# 12VPart.net
KiCad netlist of a schematic drawn in EAGLE
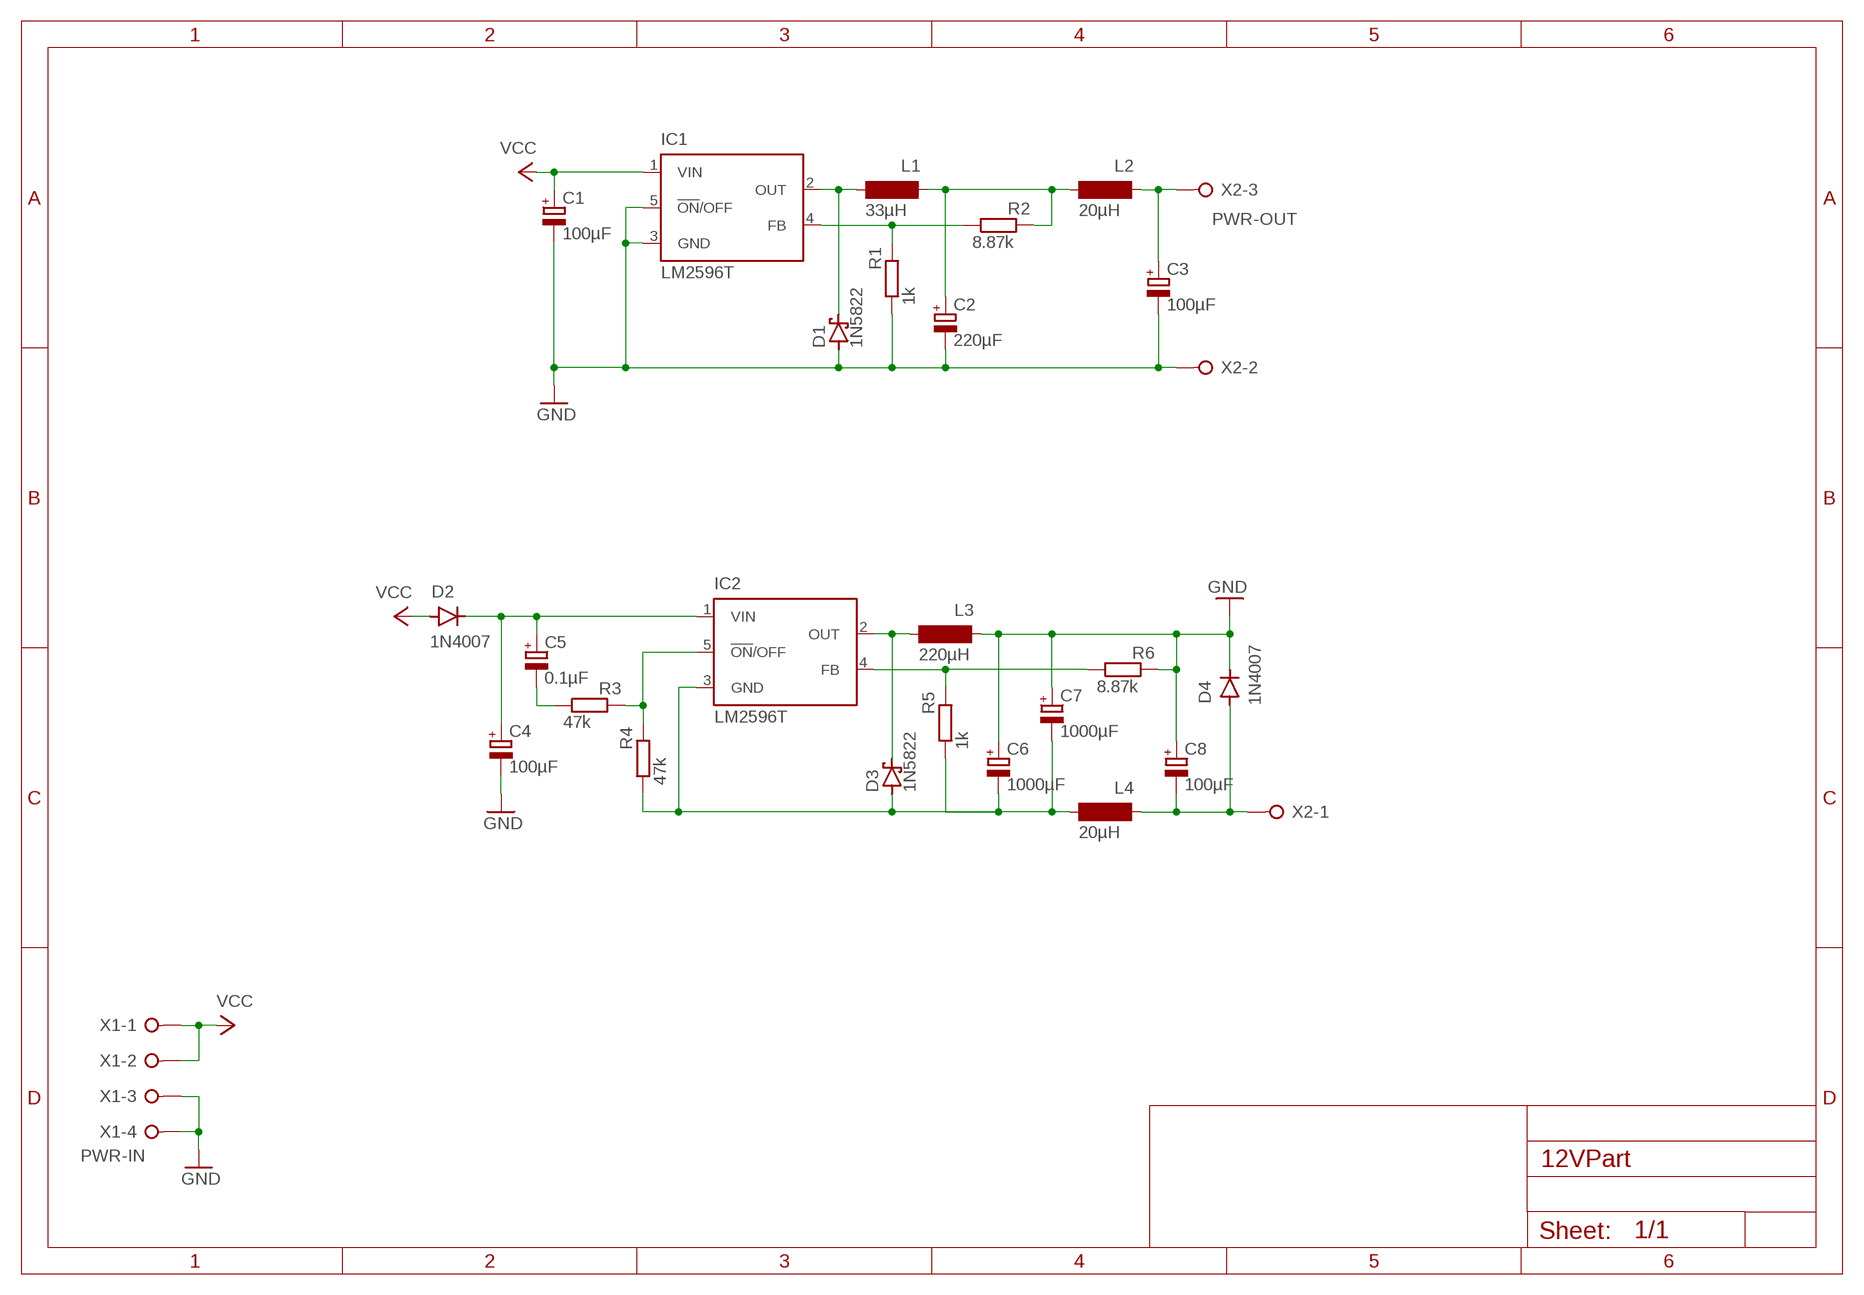
[diagram p0: schematic, sheet 1]

(export (version "E")
  (design (tool "Eeschema 10.0.6"))
  (components
    (comp (ref "C1")
      (value "100µF")
      (footprint "eagle-import:E2,5-6")
      (libsource (lib "eagle-import") (part "CPOL-EUE2.5-6"))
    )
    (comp (ref "C2")
      (value "220µF")
      (footprint "eagle-import:E2,5-6")
      (libsource (lib "eagle-import") (part "CPOL-EUE2.5-6"))
    )
    (comp (ref "C3")
      (value "100µF")
      (footprint "eagle-import:E2,5-6")
      (libsource (lib "eagle-import") (part "CPOL-EUE2.5-6"))
    )
    (comp (ref "C4")
      (value "100µF")
      (footprint "eagle-import:E2,5-6")
      (libsource (lib "eagle-import") (part "CPOL-EUE2.5-6"))
    )
    (comp (ref "C5")
      (value "0.1µF")
      (footprint "eagle-import:E2-4")
      (libsource (lib "eagle-import") (part "CPOL-EUE2-4"))
    )
    (comp (ref "C6")
      (value "1000µF")
      (footprint "eagle-import:E5-10,5")
      (libsource (lib "eagle-import") (part "CPOL-EUE5-10.5"))
    )
    (comp (ref "C7")
      (value "1000µF")
      (footprint "eagle-import:E5-10,5")
      (libsource (lib "eagle-import") (part "CPOL-EUE5-10.5"))
    )
    (comp (ref "C8")
      (value "100µF")
      (footprint "eagle-import:E2,5-6")
      (libsource (lib "eagle-import") (part "CPOL-EUE2.5-6"))
    )
    (comp (ref "D1")
      (value "1N5822")
      (footprint "eagle-import:C4111-15")
      (libsource (lib "eagle-import") (part "1N5908"))
    )
    (comp (ref "D2")
      (value "1N4007")
      (footprint "eagle-import:DO-41")
      (fields
        (field (name "DIGIKEY_PART_NUMBER") "1N4007MSCT-ND")
        (field (name "MANUFACTURER") "Micro Commercial Co")
        (field (name "CREATED_BY") "PCBLayout.com")
      )
      (libsource (lib "eagle-import") (part "1N4007"))
    )
    (comp (ref "D3")
      (value "1N5822")
      (footprint "eagle-import:C4111-15")
      (libsource (lib "eagle-import") (part "1N5908"))
    )
    (comp (ref "D4")
      (value "1N4007")
      (footprint "eagle-import:DO-41")
      (fields
        (field (name "DIGIKEY_PART_NUMBER") "1N4007MSCT-ND")
        (field (name "MANUFACTURER") "Micro Commercial Co")
        (field (name "CREATED_BY") "PCBLayout.com")
      )
      (libsource (lib "eagle-import") (part "1N4007"))
    )
    (comp (ref "IC1")
      (value "LM2596T")
      (footprint "eagle-import:T05D")
      (fields (field (name "MPN") "LM2596T-ADJ/LF02"))
      (libsource (lib "eagle-import") (part "LM2596T"))
    )
    (comp (ref "IC2")
      (value "LM2596T")
      (footprint "eagle-import:T05D")
      (fields (field (name "MPN") "LM2596T-ADJ/LF02"))
      (libsource (lib "eagle-import") (part "LM2596T"))
    )
    (comp (ref "L1")
      (value "33µH")
      (footprint "eagle-import:IND-120")
      (libsource (lib "eagle-import") (part "IND-120-330K"))
    )
    (comp (ref "L2")
      (value "20µH")
      (footprint "eagle-import:B82111B")
      (libsource (lib "eagle-import") (part "B82111B0000C020"))
    )
    (comp (ref "L3")
      (value "220µH")
      (footprint "eagle-import:11PHC")
      (libsource (lib "eagle-import") (part "11PHC-221K-50"))
    )
    (comp (ref "L4")
      (value "20µH")
      (footprint "eagle-import:B82111B")
      (libsource (lib "eagle-import") (part "B82111B0000C020"))
    )
    (comp (ref "R1")
      (value "1k")
      (footprint "eagle-import:0207_10")
      (libsource (lib "eagle-import") (part "R-EU_0207/10"))
    )
    (comp (ref "R2")
      (value "8.87k")
      (footprint "eagle-import:0207_10")
      (libsource (lib "eagle-import") (part "R-EU_0207/10"))
    )
    (comp (ref "R3")
      (value "47k")
      (footprint "eagle-import:0207_10")
      (libsource (lib "eagle-import") (part "R-EU_0207/10"))
    )
    (comp (ref "R4")
      (value "47k")
      (footprint "eagle-import:0207_10")
      (libsource (lib "eagle-import") (part "R-EU_0207/10"))
    )
    (comp (ref "R5")
      (value "1k")
      (footprint "eagle-import:0207_10")
      (libsource (lib "eagle-import") (part "R-EU_0207/10"))
    )
    (comp (ref "R6")
      (value "8.87k")
      (footprint "eagle-import:0207_10")
      (libsource (lib "eagle-import") (part "R-EU_0207/10"))
    )
    (comp (ref "X1")
      (value "PWR-IN")
      (footprint "eagle-import:W237-4P")
      (libsource (lib "eagle-import") (part "W237-04P"))
    )
    (comp (ref "X2")
      (value "PWR-OUT")
      (footprint "eagle-import:W237-133")
      (libsource (lib "eagle-import") (part "W237-03P"))
    )
  )
  (nets
    (net (code "1") (name "GND") (class "Default")
      (node (ref "C1") (pin "-") (pinfunction "-_-") (pintype "passive"))
      (node (ref "C2") (pin "-") (pinfunction "-_-") (pintype "passive"))
      (node (ref "C3") (pin "-") (pinfunction "-_-") (pintype "passive"))
      (node (ref "C4") (pin "-") (pinfunction "-_-") (pintype "passive"))
      (node (ref "C6") (pin "+") (pinfunction "+_+") (pintype "passive"))
      (node (ref "C7") (pin "+") (pinfunction "+_+") (pintype "passive"))
      (node (ref "C8") (pin "+") (pinfunction "+_+") (pintype "passive"))
      (node (ref "D1") (pin "A") (pinfunction "A_A") (pintype "passive"))
      (node (ref "D4") (pin "C") (pinfunction "C_C") (pintype "passive"))
      (node (ref "IC1") (pin "3") (pinfunction "GND_3") (pintype "power_in"))
      (node (ref "IC1") (pin "5") (pinfunction "~{ON}/OFF_5") (pintype "input"))
      (node (ref "L3") (pin "P$2") (pinfunction "2_P$2") (pintype "passive"))
      (node (ref "R1") (pin "1") (pinfunction "1_1") (pintype "passive"))
      (node (ref "R6") (pin "2") (pinfunction "2_2") (pintype "passive"))
      (node (ref "X1") (pin "3") (pinfunction "KL_3") (pintype "passive"))
      (node (ref "X1") (pin "4") (pinfunction "KL_4") (pintype "passive"))
      (node (ref "X2") (pin "2") (pinfunction "KL_2") (pintype "passive"))
    )
    (net (code "2") (name "Net-(C5-Pad-)") (class "Default")
      (node (ref "C5") (pin "-") (pinfunction "-_-") (pintype "passive"))
      (node (ref "R3") (pin "1") (pinfunction "1_1") (pintype "passive"))
    )
    (net (code "3") (name "Net-(IC1-FB)") (class "Default")
      (node (ref "IC1") (pin "4") (pinfunction "FB_4") (pintype "input"))
      (node (ref "R1") (pin "2") (pinfunction "2_2") (pintype "passive"))
      (node (ref "R2") (pin "1") (pinfunction "1_1") (pintype "passive"))
    )
    (net (code "4") (name "Net-(IC1-OUT)") (class "Default")
      (node (ref "D1") (pin "C") (pinfunction "C_C") (pintype "passive"))
      (node (ref "IC1") (pin "2") (pinfunction "OUT_2") (pintype "output"))
      (node (ref "L1") (pin "P$1") (pinfunction "1_P$1") (pintype "passive"))
    )
    (net (code "5") (name "Net-(IC2-FB)") (class "Default")
      (node (ref "IC2") (pin "4") (pinfunction "FB_4") (pintype "input"))
      (node (ref "R5") (pin "2") (pinfunction "2_2") (pintype "passive"))
      (node (ref "R6") (pin "1") (pinfunction "1_1") (pintype "passive"))
    )
    (net (code "6") (name "Net-(IC2-GND)") (class "Default")
      (node (ref "C6") (pin "-") (pinfunction "-_-") (pintype "passive"))
      (node (ref "C7") (pin "-") (pinfunction "-_-") (pintype "passive"))
      (node (ref "D3") (pin "A") (pinfunction "A_A") (pintype "passive"))
      (node (ref "IC2") (pin "3") (pinfunction "GND_3") (pintype "power_in"))
      (node (ref "L4") (pin "P$1") (pinfunction "1_P$1") (pintype "passive"))
      (node (ref "R4") (pin "1") (pinfunction "1_1") (pintype "passive"))
      (node (ref "R5") (pin "1") (pinfunction "1_1") (pintype "passive"))
    )
    (net (code "7") (name "Net-(IC2-OUT)") (class "Default")
      (node (ref "D3") (pin "C") (pinfunction "C_C") (pintype "passive"))
      (node (ref "IC2") (pin "2") (pinfunction "OUT_2") (pintype "output"))
      (node (ref "L3") (pin "P$1") (pinfunction "1_P$1") (pintype "passive"))
    )
    (net (code "8") (name "Net-(IC2-VIN)") (class "Default")
      (node (ref "C4") (pin "+") (pinfunction "+_+") (pintype "passive"))
      (node (ref "C5") (pin "+") (pinfunction "+_+") (pintype "passive"))
      (node (ref "D2") (pin "C") (pinfunction "C_C") (pintype "passive"))
      (node (ref "IC2") (pin "1") (pinfunction "VIN_1") (pintype "input"))
    )
    (net (code "9") (name "Net-(IC2-~{ON}{slash}OFF)") (class "Default")
      (node (ref "IC2") (pin "5") (pinfunction "~{ON}/OFF_5") (pintype "input"))
      (node (ref "R3") (pin "2") (pinfunction "2_2") (pintype "passive"))
      (node (ref "R4") (pin "2") (pinfunction "2_2") (pintype "passive"))
    )
    (net (code "10") (name "Net-(L1-2)") (class "Default")
      (node (ref "C2") (pin "+") (pinfunction "+_+") (pintype "passive"))
      (node (ref "L1") (pin "P$2") (pinfunction "2_P$2") (pintype "passive"))
      (node (ref "L2") (pin "P$1") (pinfunction "1_P$1") (pintype "passive"))
      (node (ref "R2") (pin "2") (pinfunction "2_2") (pintype "passive"))
    )
    (net (code "11") (name "Net-(L2-2)") (class "Default")
      (node (ref "C3") (pin "+") (pinfunction "+_+") (pintype "passive"))
      (node (ref "L2") (pin "P$2") (pinfunction "2_P$2") (pintype "passive"))
      (node (ref "X2") (pin "3") (pinfunction "KL_3") (pintype "passive"))
    )
    (net (code "12") (name "Net-(L4-2)") (class "Default")
      (node (ref "C8") (pin "-") (pinfunction "-_-") (pintype "passive"))
      (node (ref "D4") (pin "A") (pinfunction "A_A") (pintype "passive"))
      (node (ref "L4") (pin "P$2") (pinfunction "2_P$2") (pintype "passive"))
      (node (ref "X2") (pin "1") (pinfunction "KL_1") (pintype "passive"))
    )
    (net (code "13") (name "VCC") (class "Default")
      (node (ref "C1") (pin "+") (pinfunction "+_+") (pintype "passive"))
      (node (ref "D2") (pin "A") (pinfunction "A_A") (pintype "passive"))
      (node (ref "IC1") (pin "1") (pinfunction "VIN_1") (pintype "input"))
      (node (ref "X1") (pin "1") (pinfunction "KL_1") (pintype "passive"))
      (node (ref "X1") (pin "2") (pinfunction "KL_2") (pintype "passive"))
    )
  )
)
